# K06-43.net
KiCad netlist of a schematic drawn in Altium Designer
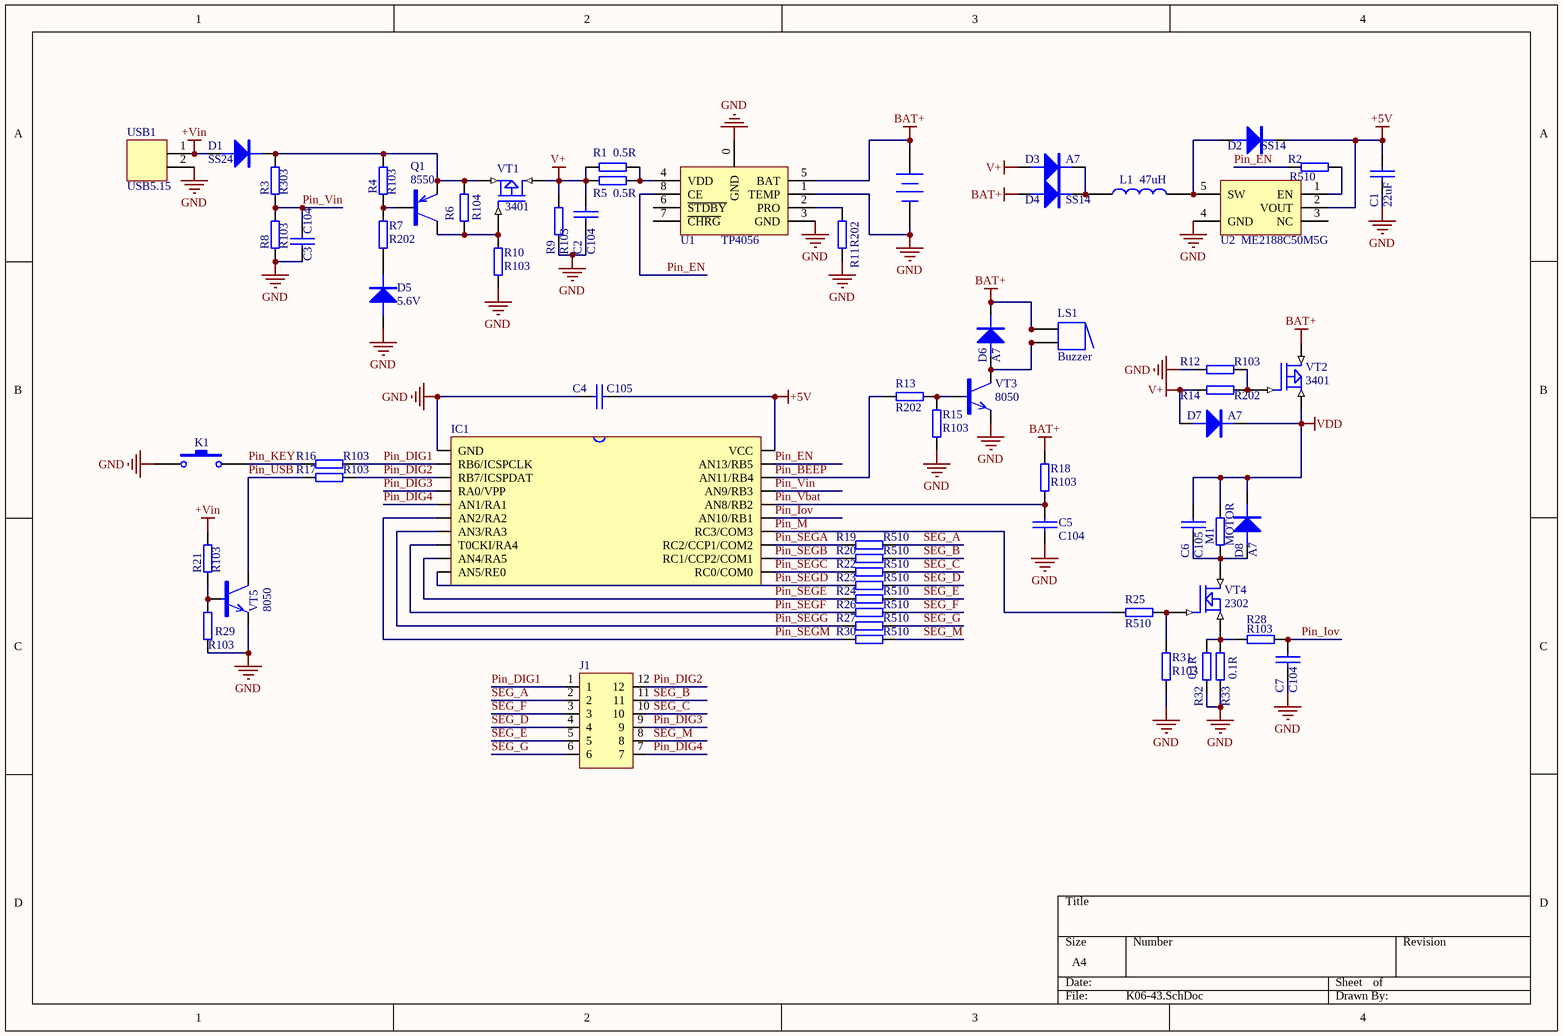
[diagram p0: K06-43.SchDoc]

(export (version "E")
  (design (tool "Eeschema 10.0.6"))
  (components
    (comp (ref "BT1")
      (value "Battery")
      (footprint "BAT")
      (fields (field (name "PUBLISHER") "Altium Limited"))
      (libsource (lib "altium-import") (part "root_3_Battery_"))
    )
    (comp (ref "C1") (value "22uF") (footprint "1206") (libsource (lib "altium-import") (part "root_0_CAP_")))
    (comp (ref "C2") (value "C104") (footprint "0603") (libsource (lib "altium-import") (part "root_2_CAP_")))
    (comp (ref "C3")
      (value "C104")
      (footprint "0805N")
      (libsource (lib "altium-import") (part "root_2_CAP_"))
    )
    (comp (ref "C4")
      (value "C105")
      (footprint "0805N")
      (libsource (lib "altium-import") (part "root_3_CAP_"))
    )
    (comp (ref "C5")
      (value "C104")
      (footprint "0603")
      (libsource (lib "altium-import") (part "root_2_mirrored_CAP_"))
    )
    (comp (ref "C6")
      (value "C105")
      (footprint "0805N")
      (libsource (lib "altium-import") (part "root_2_CAP_"))
    )
    (comp (ref "C7") (value "C104") (footprint "0603") (libsource (lib "altium-import") (part "root_2_CAP_")))
    (comp (ref "D1")
      (value "SS24")
      (footprint "DO-214AC")
      (libsource (lib "altium-import") (part "root_0_DIODE_"))
    )
    (comp (ref "D2")
      (value "SS14")
      (footprint "DO-214AC")
      (libsource (lib "altium-import") (part "root_0_DIODE_"))
    )
    (comp (ref "D3")
      (value "A7")
      (footprint "DO-214AC")
      (libsource (lib "altium-import") (part "root_0_DIODE_"))
    )
    (comp (ref "D4")
      (value "SS14")
      (footprint "DO-214AC")
      (libsource (lib "altium-import") (part "root_0_DIODE_"))
    )
    (comp (ref "D5")
      (value "5.6V")
      (footprint "4148")
      (libsource (lib "altium-import") (part "root_1_DIODE_"))
    )
    (comp (ref "D6")
      (value "A7")
      (footprint "DO-214AC")
      (description "Diode")
      (libsource (lib "MySCHLib") (part "DIODE"))
    )
    (comp (ref "D7")
      (value "A7")
      (footprint "DO-214AC")
      (libsource (lib "altium-import") (part "root_0_DIODE_"))
    )
    (comp (ref "D8")
      (value "A7")
      (footprint "DO-214AC")
      (libsource (lib "altium-import") (part "root_1_mirrored_DIODE_"))
    )
    (comp (ref "IC1") (value "~") (footprint "QSOP20") (libsource (lib "MySCHLib") (part "MCU_1713")))
    (comp (ref "J1") (value "~") (footprint "DIP254-6P") (libsource (lib "MySCHLib") (part "DB6*2")))
    (comp (ref "K1")
      (value "4*4*H")
      (footprint "D4_SMT")
      (fields (field (name "PUBLISHER") "Altium Limited"))
      (libsource (lib "altium-import") (part "root_0_SW-PB_"))
    )
    (comp (ref "L1")
      (value "47uH")
      (footprint "CD4X")
      (description "1.5A以上")
      (libsource (lib "YF SCHlib V1.00") (part "L"))
    )
    (comp (ref "LS1")
      (value "Buzzer")
      (footprint "buzzer-9.0")
      (description "Magnetic Transducer Buzzer")
      (fields (field (name "PUBLISHER") "Altium Limited"))
      (libsource (lib "Miscellaneous Devices") (part "Buzzer"))
    )
    (comp (ref "M1")
      (value "MOTOR")
      (footprint "bat")
      (libsource (lib "altium-import") (part "root_1_RES2_"))
    )
    (comp (ref "Q1") (value "8550") (footprint "sot-23") (libsource (lib "MySCHLib") (part "8550-SMT")))
    (comp (ref "R1")
      (value "0.5R")
      (footprint "0603")
      (libsource (lib "altium-import") (part "root_0_RES2_"))
    )
    (comp (ref "R2")
      (value "R510")
      (footprint "0603")
      (libsource (lib "altium-import") (part "root_0_RES2_"))
    )
    (comp (ref "R3")
      (value "R303")
      (footprint "0603")
      (libsource (lib "altium-import") (part "root_3_RES2_"))
    )
    (comp (ref "R4")
      (value "R103")
      (footprint "0603")
      (libsource (lib "altium-import") (part "root_3_RES2_"))
    )
    (comp (ref "R5")
      (value "0.5R")
      (footprint "0603")
      (libsource (lib "altium-import") (part "root_0_RES2_"))
    )
    (comp (ref "R6")
      (value "R104")
      (footprint "0603")
      (libsource (lib "altium-import") (part "root_1_RES2_"))
    )
    (comp (ref "R7")
      (value "R202")
      (footprint "0603")
      (libsource (lib "altium-import") (part "root_1_RES2_"))
    )
    (comp (ref "R8")
      (value "R103")
      (footprint "0603")
      (libsource (lib "altium-import") (part "root_3_RES2_"))
    )
    (comp (ref "R9")
      (value "R103")
      (footprint "0603")
      (libsource (lib "altium-import") (part "root_3_RES2_"))
    )
    (comp (ref "R10")
      (value "R103")
      (footprint "0603")
      (libsource (lib "altium-import") (part "root_1_RES2_"))
    )
    (comp (ref "R11")
      (value "R202")
      (footprint "0603")
      (libsource (lib "altium-import") (part "root_3_RES2_"))
    )
    (comp (ref "R12") (value "R103") (footprint "0603") (libsource (lib "YF SCHlib V1.00") (part "RES2")))
    (comp (ref "R13")
      (value "R202")
      (footprint "0603")
      (libsource (lib "altium-import") (part "root_0_mirrored_RES2_"))
    )
    (comp (ref "R14") (value "R202") (footprint "0603") (libsource (lib "YF SCHlib V1.00") (part "RES2")))
    (comp (ref "R15")
      (value "R103")
      (footprint "0603")
      (libsource (lib "altium-import") (part "root_3_mirrored_RES2_"))
    )
    (comp (ref "R16")
      (value "R103")
      (footprint "0603")
      (libsource (lib "altium-import") (part "root_2_RES2_"))
    )
    (comp (ref "R17")
      (value "R103")
      (footprint "0603")
      (libsource (lib "altium-import") (part "root_2_RES2_"))
    )
    (comp (ref "R18")
      (value "R103")
      (footprint "0603")
      (libsource (lib "altium-import") (part "root_1_RES2_"))
    )
    (comp (ref "R19")
      (value "R510")
      (footprint "0603")
      (libsource (lib "altium-import") (part "root_2_mirrored_RES2_"))
    )
    (comp (ref "R20")
      (value "R510")
      (footprint "0603")
      (libsource (lib "altium-import") (part "root_0_mirrored_RES2_"))
    )
    (comp (ref "R21")
      (value "R103")
      (footprint "0603")
      (libsource (lib "altium-import") (part "root_1_RES2_"))
    )
    (comp (ref "R22")
      (value "R510")
      (footprint "0603")
      (libsource (lib "altium-import") (part "root_2_mirrored_RES2_"))
    )
    (comp (ref "R23")
      (value "R510")
      (footprint "0603")
      (libsource (lib "altium-import") (part "root_2_mirrored_RES2_"))
    )
    (comp (ref "R24")
      (value "R510")
      (footprint "0603")
      (libsource (lib "altium-import") (part "root_2_mirrored_RES2_"))
    )
    (comp (ref "R25")
      (value "R510")
      (footprint "0603")
      (libsource (lib "altium-import") (part "root_0_mirrored_RES2_"))
    )
    (comp (ref "R26")
      (value "R510")
      (footprint "0603")
      (libsource (lib "altium-import") (part "root_2_mirrored_RES2_"))
    )
    (comp (ref "R27")
      (value "R510")
      (footprint "0603")
      (libsource (lib "altium-import") (part "root_2_mirrored_RES2_"))
    )
    (comp (ref "R28")
      (value "R103")
      (footprint "0603")
      (libsource (lib "altium-import") (part "root_0_RES2_"))
    )
    (comp (ref "R29")
      (value "R103")
      (footprint "0603")
      (libsource (lib "altium-import") (part "root_1_RES2_"))
    )
    (comp (ref "R30")
      (value "R510")
      (footprint "0603")
      (libsource (lib "altium-import") (part "root_2_mirrored_RES2_"))
    )
    (comp (ref "R31")
      (value "R103")
      (footprint "0603")
      (libsource (lib "altium-import") (part "root_3_mirrored_RES2_"))
    )
    (comp (ref "R32")
      (value "0.1R")
      (footprint "1206")
      (libsource (lib "altium-import") (part "root_1_RES2_"))
    )
    (comp (ref "R33")
      (value "0.1R")
      (footprint "1206")
      (libsource (lib "altium-import") (part "root_1_RES2_"))
    )
    (comp (ref "U1") (value "TP4056") (footprint "ESOP-8") (libsource (lib "MySCHLib") (part "TP4056")))
    (comp (ref "U2")
      (value "ME2188C50M5G")
      (footprint "SOT-23-5")
      (libsource (lib "MySCHLib") (part "TP5303"))
    )
    (comp (ref "USB1")
      (value "USB5.15")
      (footprint "BAT")
      (libsource (lib "altium-import") (part "root_0_USB2_"))
    )
    (comp (ref "VT1") (value "3401") (footprint "SOT-23") (libsource (lib "MySCHLib") (part "MOSFET P")))
    (comp (ref "VT2") (value "3401") (footprint "SOT-23") (libsource (lib "MySCHLib") (part "MOSFET P")))
    (comp (ref "VT3") (value "8050") (footprint "SOT-23") (libsource (lib "MySCHLib") (part "8050-SMT")))
    (comp (ref "VT4")
      (value "2302")
      (footprint "sot-23")
      (libsource (lib "altium-import") (part "root_0_MOSFET N_"))
    )
    (comp (ref "VT5") (value "8050") (footprint "SOT-23") (libsource (lib "MySCHLib") (part "8050-SMT")))
  )
  (nets
    (net (code "1") (name "+5V") (class "Default")
      (node (ref "C1") (pin "1") (pinfunction "1_1") (pintype "passive"))
      (node (ref "C4") (pin "1") (pinfunction "1_1") (pintype "passive"))
      (node (ref "D2") (pin "2") (pinfunction "K_2") (pintype "passive"))
      (node (ref "IC1") (pin "20") (pinfunction "VCC_20") (pintype "passive"))
      (node (ref "U2") (pin "2") (pinfunction "VOUT_2") (pintype "passive"))
    )
    (net (code "2") (name "+Vin") (class "Default")
      (node (ref "D1") (pin "1") (pinfunction "A_1") (pintype "passive"))
      (node (ref "R21") (pin "2") (pinfunction "2_2") (pintype "passive"))
      (node (ref "USB1") (pin "1") (pinfunction "1_1") (pintype "passive"))
    )
    (net (code "3") (name "/Pin_BEEP") (class "Default")
      (node (ref "IC1") (pin "18") (pinfunction "AN11/RB4_18") (pintype "passive"))
      (node (ref "R13") (pin "2") (pinfunction "2_2") (pintype "passive"))
    )
    (net (code "4") (name "/Pin_DIG1") (class "Default")
      (node (ref "IC1") (pin "2") (pinfunction "RB6/ICSPCLK_2") (pintype "passive"))
      (node (ref "J1") (pin "1") (pinfunction "1_1") (pintype "passive"))
      (node (ref "R16") (pin "1") (pinfunction "1_1") (pintype "passive"))
    )
    (net (code "5") (name "/Pin_DIG2") (class "Default")
      (node (ref "IC1") (pin "3") (pinfunction "RB7/ICSPDAT_3") (pintype "passive"))
      (node (ref "J1") (pin "12") (pinfunction "12_12") (pintype "passive"))
      (node (ref "R17") (pin "1") (pinfunction "1_1") (pintype "passive"))
    )
    (net (code "6") (name "/Pin_DIG3") (class "Default")
      (node (ref "IC1") (pin "4") (pinfunction "RA0/VPP_4") (pintype "passive"))
      (node (ref "J1") (pin "9") (pinfunction "9_9") (pintype "passive"))
    )
    (net (code "7") (name "/Pin_DIG4") (class "Default")
      (node (ref "IC1") (pin "5") (pinfunction "AN1/RA1_5") (pintype "passive"))
      (node (ref "J1") (pin "7") (pinfunction "7_7") (pintype "passive"))
    )
    (net (code "8") (name "/Pin_EN") (class "Default")
      (node (ref "IC1") (pin "19") (pinfunction "AN13/RB5_19") (pintype "passive"))
      (node (ref "R2") (pin "1") (pinfunction "1_1") (pintype "passive"))
      (node (ref "U1") (pin "8") (pinfunction "CE_8") (pintype "passive"))
    )
    (net (code "9") (name "/Pin_Iov") (class "Default")
      (node (ref "C7") (pin "2") (pinfunction "2_2") (pintype "passive"))
      (node (ref "IC1") (pin "15") (pinfunction "AN10/RB1_15") (pintype "passive"))
      (node (ref "R28") (pin "2") (pinfunction "2_2") (pintype "passive"))
    )
    (net (code "10") (name "/Pin_KEY") (class "Default")
      (node (ref "K1") (pin "2") (pinfunction "2_2") (pintype "passive"))
      (node (ref "R16") (pin "2") (pinfunction "2_2") (pintype "passive"))
    )
    (net (code "11") (name "/Pin_M") (class "Default")
      (node (ref "IC1") (pin "14") (pinfunction "RC3/COM3_14") (pintype "passive"))
      (node (ref "R25") (pin "2") (pinfunction "2_2") (pintype "passive"))
    )
    (net (code "12") (name "/Pin_SEGA") (class "Default")
      (node (ref "IC1") (pin "13") (pinfunction "RC2/CCP1/COM2_13") (pintype "passive"))
      (node (ref "R19") (pin "1") (pinfunction "1_1") (pintype "passive"))
    )
    (net (code "13") (name "/Pin_SEGB") (class "Default")
      (node (ref "IC1") (pin "12") (pinfunction "RC1/CCP2/COM1_12") (pintype "passive"))
      (node (ref "R20") (pin "2") (pinfunction "2_2") (pintype "passive"))
    )
    (net (code "14") (name "/Pin_SEGC") (class "Default")
      (node (ref "IC1") (pin "11") (pinfunction "RC0/COM0_11") (pintype "passive"))
      (node (ref "R22") (pin "1") (pinfunction "1_1") (pintype "passive"))
    )
    (net (code "15") (name "/Pin_SEGD") (class "Default")
      (node (ref "IC1") (pin "10") (pinfunction "AN5/RE0_10") (pintype "passive"))
      (node (ref "R23") (pin "1") (pinfunction "1_1") (pintype "passive"))
    )
    (net (code "16") (name "/Pin_SEGE") (class "Default")
      (node (ref "IC1") (pin "9") (pinfunction "AN4/RA5_9") (pintype "passive"))
      (node (ref "R24") (pin "1") (pinfunction "1_1") (pintype "passive"))
    )
    (net (code "17") (name "/Pin_SEGF") (class "Default")
      (node (ref "IC1") (pin "8") (pinfunction "T0CKI/RA4_8") (pintype "passive"))
      (node (ref "R26") (pin "1") (pinfunction "1_1") (pintype "passive"))
    )
    (net (code "18") (name "/Pin_SEGG") (class "Default")
      (node (ref "IC1") (pin "7") (pinfunction "AN3/RA3_7") (pintype "passive"))
      (node (ref "R27") (pin "1") (pinfunction "1_1") (pintype "passive"))
    )
    (net (code "19") (name "/Pin_SEGM") (class "Default")
      (node (ref "IC1") (pin "6") (pinfunction "AN2/RA2_6") (pintype "passive"))
      (node (ref "R30") (pin "1") (pinfunction "1_1") (pintype "passive"))
    )
    (net (code "20") (name "/Pin_USB") (class "Default")
      (node (ref "R17") (pin "2") (pinfunction "2_2") (pintype "passive"))
      (node (ref "VT5") (pin "3") (pinfunction "C_3") (pintype "passive"))
    )
    (net (code "21") (name "/Pin_Vbat") (class "Default")
      (node (ref "C5") (pin "2") (pinfunction "2_2") (pintype "passive"))
      (node (ref "IC1") (pin "16") (pinfunction "AN8/RB2_16") (pintype "passive"))
      (node (ref "R18") (pin "1") (pinfunction "1_1") (pintype "passive"))
    )
    (net (code "22") (name "/Pin_Vin") (class "Default")
      (node (ref "C3") (pin "2") (pinfunction "2_2") (pintype "passive"))
      (node (ref "IC1") (pin "17") (pinfunction "AN9/RB3_17") (pintype "passive"))
      (node (ref "R3") (pin "2") (pinfunction "2_2") (pintype "passive"))
      (node (ref "R8") (pin "1") (pinfunction "1_1") (pintype "passive"))
    )
    (net (code "23") (name "/SEG_A") (class "Default")
      (node (ref "J1") (pin "2") (pinfunction "2_2") (pintype "passive"))
      (node (ref "R19") (pin "2") (pinfunction "2_2") (pintype "passive"))
    )
    (net (code "24") (name "/SEG_B") (class "Default")
      (node (ref "J1") (pin "11") (pinfunction "11_11") (pintype "passive"))
      (node (ref "R20") (pin "1") (pinfunction "1_1") (pintype "passive"))
    )
    (net (code "25") (name "/SEG_C") (class "Default")
      (node (ref "J1") (pin "10") (pinfunction "10_10") (pintype "passive"))
      (node (ref "R22") (pin "2") (pinfunction "2_2") (pintype "passive"))
    )
    (net (code "26") (name "/SEG_D") (class "Default")
      (node (ref "J1") (pin "4") (pinfunction "4_4") (pintype "passive"))
      (node (ref "R23") (pin "2") (pinfunction "2_2") (pintype "passive"))
    )
    (net (code "27") (name "/SEG_E") (class "Default")
      (node (ref "J1") (pin "5") (pinfunction "5_5") (pintype "passive"))
      (node (ref "R24") (pin "2") (pinfunction "2_2") (pintype "passive"))
    )
    (net (code "28") (name "/SEG_F") (class "Default")
      (node (ref "J1") (pin "3") (pinfunction "3_3") (pintype "passive"))
      (node (ref "R26") (pin "2") (pinfunction "2_2") (pintype "passive"))
    )
    (net (code "29") (name "/SEG_G") (class "Default")
      (node (ref "J1") (pin "6") (pinfunction "6_6") (pintype "passive"))
      (node (ref "R27") (pin "2") (pinfunction "2_2") (pintype "passive"))
    )
    (net (code "30") (name "/SEG_M") (class "Default")
      (node (ref "J1") (pin "8") (pinfunction "8_8") (pintype "passive"))
      (node (ref "R30") (pin "2") (pinfunction "2_2") (pintype "passive"))
    )
    (net (code "31") (name "BAT+") (class "Default")
      (node (ref "BT1") (pin "1") (pinfunction "+_1") (pintype "passive"))
      (node (ref "D4") (pin "1") (pinfunction "A_1") (pintype "passive"))
      (node (ref "D6") (pin "2") (pinfunction "K_2") (pintype "passive"))
      (node (ref "LS1") (pin "1") (pinfunction "1_1") (pintype "passive"))
      (node (ref "R18") (pin "2") (pinfunction "2_2") (pintype "passive"))
      (node (ref "U1") (pin "5") (pinfunction "BAT_5") (pintype "passive"))
      (node (ref "VT2") (pin "3") (pinfunction "D_3") (pintype "input"))
    )
    (net (code "32") (name "GND") (class "Default")
      (node (ref "BT1") (pin "2") (pinfunction "-_2") (pintype "passive"))
      (node (ref "C1") (pin "2") (pinfunction "2_2") (pintype "passive"))
      (node (ref "C2") (pin "1") (pinfunction "1_1") (pintype "passive"))
      (node (ref "C3") (pin "1") (pinfunction "1_1") (pintype "passive"))
      (node (ref "C4") (pin "2") (pinfunction "2_2") (pintype "passive"))
      (node (ref "C5") (pin "1") (pinfunction "1_1") (pintype "passive"))
      (node (ref "C7") (pin "1") (pinfunction "1_1") (pintype "passive"))
      (node (ref "D5") (pin "1") (pinfunction "A_1") (pintype "passive"))
      (node (ref "IC1") (pin "1") (pinfunction "GND_1") (pintype "passive"))
      (node (ref "K1") (pin "1") (pinfunction "1_1") (pintype "passive"))
      (node (ref "R10") (pin "1") (pinfunction "1_1") (pintype "passive"))
      (node (ref "R11") (pin "2") (pinfunction "2_2") (pintype "passive"))
      (node (ref "R12") (pin "2") (pinfunction "2_2") (pintype "passive"))
      (node (ref "R15") (pin "2") (pinfunction "2_2") (pintype "passive"))
      (node (ref "R29") (pin "1") (pinfunction "1_1") (pintype "passive"))
      (node (ref "R31") (pin "2") (pinfunction "2_2") (pintype "passive"))
      (node (ref "R32") (pin "1") (pinfunction "1_1") (pintype "passive"))
      (node (ref "R33") (pin "1") (pinfunction "1_1") (pintype "passive"))
      (node (ref "R8") (pin "2") (pinfunction "2_2") (pintype "passive"))
      (node (ref "R9") (pin "2") (pinfunction "2_2") (pintype "passive"))
      (node (ref "U1") (pin "0") (pinfunction "GND_0") (pintype "passive"))
      (node (ref "U1") (pin "1") (pinfunction "TEMP_1") (pintype "passive"))
      (node (ref "U1") (pin "3") (pinfunction "GND_3") (pintype "passive"))
      (node (ref "U2") (pin "4") (pinfunction "GND_4") (pintype "passive"))
      (node (ref "USB1") (pin "2") (pinfunction "2_2") (pintype "passive"))
      (node (ref "VT3") (pin "2") (pinfunction "E_2") (pintype "passive"))
      (node (ref "VT5") (pin "2") (pinfunction "E_2") (pintype "passive"))
    )
    (net (code "33") (name "Net-(D1-K)") (class "Default")
      (node (ref "D1") (pin "2") (pinfunction "K_2") (pintype "passive"))
      (node (ref "Q1") (pin "2") (pinfunction "E_2") (pintype "passive"))
      (node (ref "R3") (pin "1") (pinfunction "1_1") (pintype "passive"))
      (node (ref "R4") (pin "1") (pinfunction "1_1") (pintype "passive"))
      (node (ref "R6") (pin "2") (pinfunction "2_2") (pintype "passive"))
      (node (ref "VT1") (pin "2") (pinfunction "S_2") (pintype "input"))
    )
    (net (code "34") (name "Net-(D2-A)") (class "Default")
      (node (ref "D2") (pin "1") (pinfunction "A_1") (pintype "passive"))
      (node (ref "L1") (pin "2") (pinfunction "2_2") (pintype "passive"))
      (node (ref "U2") (pin "5") (pinfunction "SW_5") (pintype "passive"))
    )
    (net (code "35") (name "Net-(D3-K)") (class "Default")
      (node (ref "D3") (pin "2") (pinfunction "K_2") (pintype "passive"))
      (node (ref "D4") (pin "2") (pinfunction "K_2") (pintype "passive"))
      (node (ref "L1") (pin "1") (pinfunction "1_1") (pintype "passive"))
    )
    (net (code "36") (name "Net-(D5-K)") (class "Default")
      (node (ref "D5") (pin "2") (pinfunction "K_2") (pintype "passive"))
      (node (ref "R7") (pin "1") (pinfunction "1_1") (pintype "passive"))
    )
    (net (code "37") (name "Net-(D6-A)") (class "Default")
      (node (ref "D6") (pin "1") (pinfunction "A_1") (pintype "passive"))
      (node (ref "LS1") (pin "2") (pinfunction "2_2") (pintype "passive"))
      (node (ref "VT3") (pin "3") (pinfunction "C_3") (pintype "passive"))
    )
    (net (code "38") (name "Net-(D8-A)") (class "Default")
      (node (ref "C6") (pin "1") (pinfunction "1_1") (pintype "passive"))
      (node (ref "D8") (pin "1") (pinfunction "A_1") (pintype "passive"))
      (node (ref "M1") (pin "1") (pinfunction "1_1") (pintype "passive"))
      (node (ref "VT4") (pin "3") (pinfunction "D_3") (pintype "input"))
    )
    (net (code "39") (name "Net-(Q1-B)") (class "Default")
      (node (ref "Q1") (pin "1") (pinfunction "B_1") (pintype "passive"))
      (node (ref "R4") (pin "2") (pinfunction "2_2") (pintype "passive"))
      (node (ref "R7") (pin "2") (pinfunction "2_2") (pintype "passive"))
    )
    (net (code "40") (name "Net-(Q1-C)") (class "Default")
      (node (ref "Q1") (pin "3") (pinfunction "C_3") (pintype "passive"))
      (node (ref "R10") (pin "2") (pinfunction "2_2") (pintype "passive"))
      (node (ref "R6") (pin "1") (pinfunction "1_1") (pintype "passive"))
      (node (ref "VT1") (pin "1") (pinfunction "G_1") (pintype "input"))
    )
    (net (code "41") (name "Net-(U1-PRO)") (class "Default")
      (node (ref "R11") (pin "1") (pinfunction "1_1") (pintype "passive"))
      (node (ref "U1") (pin "2") (pinfunction "PRO_2") (pintype "passive"))
    )
    (net (code "42") (name "Net-(U1-VDD)") (class "Default")
      (node (ref "R1") (pin "2") (pinfunction "2_2") (pintype "passive"))
      (node (ref "R5") (pin "2") (pinfunction "2_2") (pintype "passive"))
      (node (ref "U1") (pin "4") (pinfunction "VDD_4") (pintype "passive"))
    )
    (net (code "43") (name "Net-(U2-EN)") (class "Default")
      (node (ref "R2") (pin "2") (pinfunction "2_2") (pintype "passive"))
      (node (ref "U2") (pin "1") (pinfunction "EN_1") (pintype "passive"))
    )
    (net (code "44") (name "Net-(VT2-G)") (class "Default")
      (node (ref "R12") (pin "1") (pinfunction "1_1") (pintype "passive"))
      (node (ref "R14") (pin "2") (pinfunction "2_2") (pintype "passive"))
      (node (ref "VT2") (pin "1") (pinfunction "G_1") (pintype "input"))
    )
    (net (code "45") (name "Net-(VT3-B)") (class "Default")
      (node (ref "R13") (pin "1") (pinfunction "1_1") (pintype "passive"))
      (node (ref "R15") (pin "1") (pinfunction "1_1") (pintype "passive"))
      (node (ref "VT3") (pin "1") (pinfunction "B_1") (pintype "passive"))
    )
    (net (code "46") (name "Net-(VT4-G)") (class "Default")
      (node (ref "R25") (pin "1") (pinfunction "1_1") (pintype "passive"))
      (node (ref "R31") (pin "1") (pinfunction "1_1") (pintype "passive"))
      (node (ref "VT4") (pin "1") (pinfunction "G_1") (pintype "input"))
    )
    (net (code "47") (name "Net-(VT4-S)") (class "Default")
      (node (ref "R28") (pin "1") (pinfunction "1_1") (pintype "passive"))
      (node (ref "R32") (pin "2") (pinfunction "2_2") (pintype "passive"))
      (node (ref "R33") (pin "2") (pinfunction "2_2") (pintype "passive"))
      (node (ref "VT4") (pin "2") (pinfunction "S_2") (pintype "input"))
    )
    (net (code "48") (name "Net-(VT5-B)") (class "Default")
      (node (ref "R21") (pin "1") (pinfunction "1_1") (pintype "passive"))
      (node (ref "R29") (pin "2") (pinfunction "2_2") (pintype "passive"))
      (node (ref "VT5") (pin "1") (pinfunction "B_1") (pintype "passive"))
    )
    (net (code "49") (name "V+") (class "Default")
      (node (ref "C2") (pin "2") (pinfunction "2_2") (pintype "passive"))
      (node (ref "D3") (pin "1") (pinfunction "A_1") (pintype "passive"))
      (node (ref "D7") (pin "1") (pinfunction "A_1") (pintype "passive"))
      (node (ref "R1") (pin "1") (pinfunction "1_1") (pintype "passive"))
      (node (ref "R14") (pin "1") (pinfunction "1_1") (pintype "passive"))
      (node (ref "R5") (pin "1") (pinfunction "1_1") (pintype "passive"))
      (node (ref "R9") (pin "1") (pinfunction "1_1") (pintype "passive"))
      (node (ref "VT1") (pin "3") (pinfunction "D_3") (pintype "input"))
    )
    (net (code "50") (name "VDD") (class "Default")
      (node (ref "C6") (pin "2") (pinfunction "2_2") (pintype "passive"))
      (node (ref "D7") (pin "2") (pinfunction "K_2") (pintype "passive"))
      (node (ref "D8") (pin "2") (pinfunction "K_2") (pintype "passive"))
      (node (ref "M1") (pin "2") (pinfunction "2_2") (pintype "passive"))
      (node (ref "VT2") (pin "2") (pinfunction "S_2") (pintype "input"))
    )
    (net (code "51") (name "unconnected-(U1-~{CHRG}-Pad7)") (class "Default")
      (node (ref "U1") (pin "7") (pinfunction "~{CHRG}_7") (pintype "passive"))
    )
    (net (code "52") (name "unconnected-(U1-~{STDBY}-Pad6)") (class "Default")
      (node (ref "U1") (pin "6") (pinfunction "~{STDBY}_6") (pintype "passive"))
    )
    (net (code "53") (name "unconnected-(U2-NC-Pad3)") (class "Default")
      (node (ref "U2") (pin "3") (pinfunction "NC_3") (pintype "passive"))
    )
  )
)
